# NanoEthernet.net
KiCad netlist of a schematic drawn in EAGLE
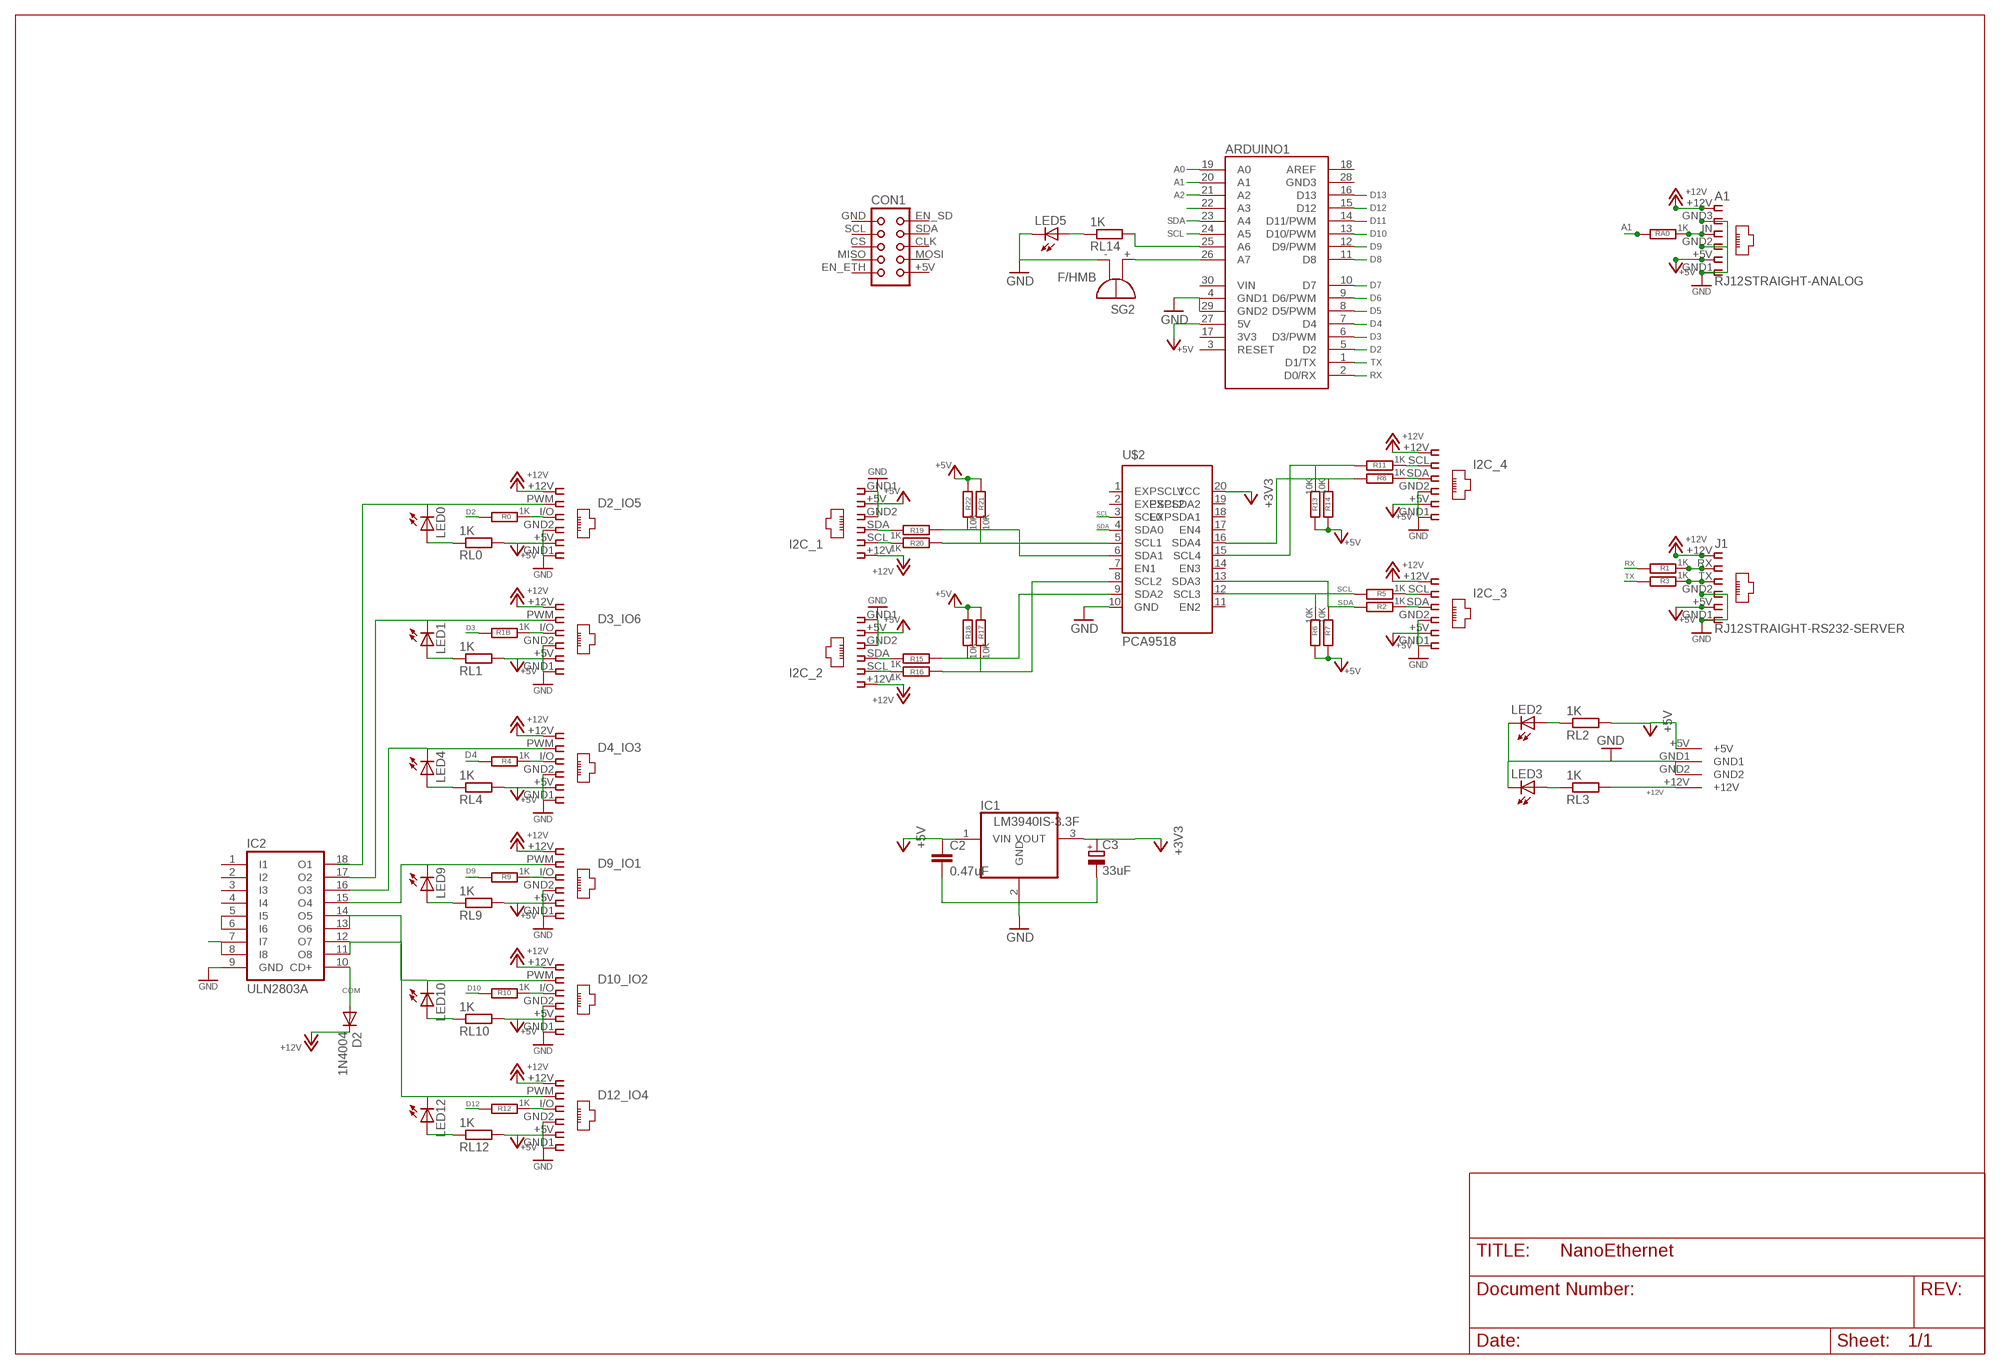
[diagram p0: schematic, sheet 1]

(export (version "E")
  (design (tool "Eeschema 10.0.6"))
  (components
    (comp (ref "A1")
      (value "RJ12STRAIGHT-ANALOG")
      (footprint "eagle-import:RJ12-STRAIGHT-ANALOG")
      (libsource (lib "eagle-import") (part "RJ12STRAIGHT-ANALOG"))
    )
    (comp (ref "ARDUINO1")
      (value "ARDUINO_NANO")
      (footprint "eagle-import:ARDUINO_NANO")
      (libsource (lib "eagle-import") (part "ARDUINO_NANO"))
    )
    (comp (ref "C2")
      (value "0.47uF")
      (footprint "eagle-import:C1206")
      (libsource (lib "eagle-import") (part "C-EUC1206"))
    )
    (comp (ref "C3")
      (value "33uF")
      (footprint "eagle-import:E3,5-8")
      (libsource (lib "eagle-import") (part "CPOL-EUE3.5-8"))
    )
    (comp (ref "CON1")
      (value "CON10EXT")
      (footprint "eagle-import:CON10EXT")
      (libsource (lib "eagle-import") (part "CON10EXT"))
    )
    (comp (ref "D2")
      (value "1N4004")
      (footprint "eagle-import:DO41-10")
      (libsource (lib "eagle-import") (part "1N4004"))
    )
    (comp (ref "D2_IO5")
      (value "IO5")
      (footprint "eagle-import:RJ12-STRAIGHT")
      (libsource (lib "eagle-import") (part "RJ12STRAIGHT"))
    )
    (comp (ref "D3_IO6")
      (value "IO6")
      (footprint "eagle-import:RJ12-STRAIGHT")
      (libsource (lib "eagle-import") (part "RJ12STRAIGHT"))
    )
    (comp (ref "D4_IO3")
      (value "IO3")
      (footprint "eagle-import:RJ12-STRAIGHT")
      (libsource (lib "eagle-import") (part "RJ12STRAIGHT"))
    )
    (comp (ref "D9_IO1")
      (value "IO1")
      (footprint "eagle-import:RJ12-STRAIGHT")
      (libsource (lib "eagle-import") (part "RJ12STRAIGHT"))
    )
    (comp (ref "D10_IO2")
      (value "IO2")
      (footprint "eagle-import:RJ12-STRAIGHT")
      (libsource (lib "eagle-import") (part "RJ12STRAIGHT"))
    )
    (comp (ref "D12_IO4")
      (value "IO4")
      (footprint "eagle-import:RJ12-STRAIGHT")
      (libsource (lib "eagle-import") (part "RJ12STRAIGHT"))
    )
    (comp (ref "I2C_1")
      (value "I2C")
      (footprint "eagle-import:RJ12-STRAIGHT-I2C")
      (libsource (lib "eagle-import") (part "RJ12STRAIGHT-I2C"))
    )
    (comp (ref "I2C_2")
      (value "I2C")
      (footprint "eagle-import:RJ12-STRAIGHT-I2C")
      (libsource (lib "eagle-import") (part "RJ12STRAIGHT-I2C"))
    )
    (comp (ref "I2C_3")
      (value "I2C")
      (footprint "eagle-import:RJ12-STRAIGHT-I2C")
      (libsource (lib "eagle-import") (part "RJ12STRAIGHT-I2C"))
    )
    (comp (ref "I2C_4")
      (value "I2C")
      (footprint "eagle-import:RJ12-STRAIGHT-I2C")
      (libsource (lib "eagle-import") (part "RJ12STRAIGHT-I2C"))
    )
    (comp (ref "IC1")
      (value "LM3940IS-3.3F")
      (footprint "eagle-import:DD-3")
      (fields (field (name "MF") "TEXAS INSTRUMENTS") (field (name "MPN") "REG1117FAKTTT"))
      (libsource (lib "eagle-import") (part "LM3940IS-3.3F"))
    )
    (comp (ref "IC2")
      (value "ULN2803A")
      (footprint "eagle-import:SO18W")
      (libsource (lib "eagle-import") (part "ULN2803A"))
    )
    (comp (ref "J1")
      (value "RJ12STRAIGHT-RS232-SERVER")
      (footprint "eagle-import:RJ12-STRAIGHT-RS232")
      (libsource (lib "eagle-import") (part "RJ12STRAIGHT-RS232-SERVER"))
    )
    (comp (ref "LED0")
      (value "LED3MM")
      (footprint "eagle-import:LED3MM")
      (libsource (lib "eagle-import") (part "LED3MM"))
    )
    (comp (ref "LED1")
      (value "LED3MM")
      (footprint "eagle-import:LED3MM")
      (libsource (lib "eagle-import") (part "LED3MM"))
    )
    (comp (ref "LED2")
      (value "LED3MM")
      (footprint "eagle-import:LED3MM")
      (libsource (lib "eagle-import") (part "LED3MM"))
    )
    (comp (ref "LED3")
      (value "LED3MM")
      (footprint "eagle-import:LED3MM")
      (libsource (lib "eagle-import") (part "LED3MM"))
    )
    (comp (ref "LED4")
      (value "LED3MM")
      (footprint "eagle-import:LED3MM")
      (libsource (lib "eagle-import") (part "LED3MM"))
    )
    (comp (ref "LED5")
      (value "LED3MM")
      (footprint "eagle-import:LED3MM")
      (libsource (lib "eagle-import") (part "LED3MM"))
    )
    (comp (ref "LED9")
      (value "LED3MM")
      (footprint "eagle-import:LED3MM")
      (libsource (lib "eagle-import") (part "LED3MM"))
    )
    (comp (ref "LED10")
      (value "LED3MM")
      (footprint "eagle-import:LED3MM")
      (libsource (lib "eagle-import") (part "LED3MM"))
    )
    (comp (ref "LED12")
      (value "LED3MM")
      (footprint "eagle-import:LED3MM")
      (libsource (lib "eagle-import") (part "LED3MM"))
    )
    (comp (ref "R0")
      (value "1K")
      (footprint "eagle-import:M1206")
      (libsource (lib "eagle-import") (part "R-EU_M1206"))
    )
    (comp (ref "R1")
      (value "1K")
      (footprint "eagle-import:M1206")
      (libsource (lib "eagle-import") (part "R-EU_M1206"))
    )
    (comp (ref "R1B")
      (value "1K")
      (footprint "eagle-import:M1206")
      (libsource (lib "eagle-import") (part "R-EU_M1206"))
    )
    (comp (ref "R2")
      (value "1K")
      (footprint "eagle-import:M1206")
      (libsource (lib "eagle-import") (part "R-EU_M1206"))
    )
    (comp (ref "R3")
      (value "1K")
      (footprint "eagle-import:M1206")
      (libsource (lib "eagle-import") (part "R-EU_M1206"))
    )
    (comp (ref "R4")
      (value "1K")
      (footprint "eagle-import:M1206")
      (libsource (lib "eagle-import") (part "R-EU_M1206"))
    )
    (comp (ref "R5")
      (value "1K")
      (footprint "eagle-import:M1206")
      (libsource (lib "eagle-import") (part "R-EU_M1206"))
    )
    (comp (ref "R6")
      (value "10K")
      (footprint "eagle-import:M1206")
      (libsource (lib "eagle-import") (part "R-EU_M1206"))
    )
    (comp (ref "R7")
      (value "10K")
      (footprint "eagle-import:M1206")
      (libsource (lib "eagle-import") (part "R-EU_M1206"))
    )
    (comp (ref "R8")
      (value "1K")
      (footprint "eagle-import:M1206")
      (libsource (lib "eagle-import") (part "R-EU_M1206"))
    )
    (comp (ref "R9")
      (value "1K")
      (footprint "eagle-import:M1206")
      (libsource (lib "eagle-import") (part "R-EU_M1206"))
    )
    (comp (ref "R10")
      (value "1K")
      (footprint "eagle-import:M1206")
      (libsource (lib "eagle-import") (part "R-EU_M1206"))
    )
    (comp (ref "R11")
      (value "1K")
      (footprint "eagle-import:M1206")
      (libsource (lib "eagle-import") (part "R-EU_M1206"))
    )
    (comp (ref "R12")
      (value "1K")
      (footprint "eagle-import:M1206")
      (libsource (lib "eagle-import") (part "R-EU_M1206"))
    )
    (comp (ref "R13")
      (value "10K")
      (footprint "eagle-import:M1206")
      (libsource (lib "eagle-import") (part "R-EU_M1206"))
    )
    (comp (ref "R14")
      (value "10K")
      (footprint "eagle-import:M1206")
      (libsource (lib "eagle-import") (part "R-EU_M1206"))
    )
    (comp (ref "R15")
      (value "1K")
      (footprint "eagle-import:M1206")
      (libsource (lib "eagle-import") (part "R-EU_M1206"))
    )
    (comp (ref "R16")
      (value "1K")
      (footprint "eagle-import:M1206")
      (libsource (lib "eagle-import") (part "R-EU_M1206"))
    )
    (comp (ref "R17")
      (value "10K")
      (footprint "eagle-import:M1206")
      (libsource (lib "eagle-import") (part "R-EU_M1206"))
    )
    (comp (ref "R18")
      (value "10K")
      (footprint "eagle-import:M1206")
      (libsource (lib "eagle-import") (part "R-EU_M1206"))
    )
    (comp (ref "R19")
      (value "1K")
      (footprint "eagle-import:M1206")
      (libsource (lib "eagle-import") (part "R-EU_M1206"))
    )
    (comp (ref "R20")
      (value "1K")
      (footprint "eagle-import:M1206")
      (libsource (lib "eagle-import") (part "R-EU_M1206"))
    )
    (comp (ref "R21")
      (value "10K")
      (footprint "eagle-import:M1206")
      (libsource (lib "eagle-import") (part "R-EU_M1206"))
    )
    (comp (ref "R22")
      (value "10K")
      (footprint "eagle-import:M1206")
      (libsource (lib "eagle-import") (part "R-EU_M1206"))
    )
    (comp (ref "RA0")
      (value "1K")
      (footprint "eagle-import:M1206")
      (libsource (lib "eagle-import") (part "R-EU_M1206"))
    )
    (comp (ref "RL0")
      (value "1K")
      (footprint "eagle-import:M1206")
      (libsource (lib "eagle-import") (part "R-EU_M1206"))
    )
    (comp (ref "RL1")
      (value "1K")
      (footprint "eagle-import:M1206")
      (libsource (lib "eagle-import") (part "R-EU_M1206"))
    )
    (comp (ref "RL2")
      (value "1K")
      (footprint "eagle-import:M1206")
      (libsource (lib "eagle-import") (part "R-EU_M1206"))
    )
    (comp (ref "RL3")
      (value "1K")
      (footprint "eagle-import:M1206")
      (libsource (lib "eagle-import") (part "R-EU_M1206"))
    )
    (comp (ref "RL4")
      (value "1K")
      (footprint "eagle-import:M1206")
      (libsource (lib "eagle-import") (part "R-EU_M1206"))
    )
    (comp (ref "RL9")
      (value "1K")
      (footprint "eagle-import:M1206")
      (libsource (lib "eagle-import") (part "R-EU_M1206"))
    )
    (comp (ref "RL10")
      (value "1K")
      (footprint "eagle-import:M1206")
      (libsource (lib "eagle-import") (part "R-EU_M1206"))
    )
    (comp (ref "RL12")
      (value "1K")
      (footprint "eagle-import:M1206")
      (libsource (lib "eagle-import") (part "R-EU_M1206"))
    )
    (comp (ref "RL14")
      (value "1K")
      (footprint "eagle-import:M1206")
      (libsource (lib "eagle-import") (part "R-EU_M1206"))
    )
    (comp (ref "SG2")
      (value "F/HMB")
      (footprint "eagle-import:F_HMB")
      (libsource (lib "eagle-import") (part "F/HMB"))
    )
    (comp (ref "U$1")
      (value "KPJX-4S-S")
      (footprint "eagle-import:KPJX-4S-S")
      (libsource (lib "eagle-import") (part "KPJX-4S-S"))
    )
    (comp (ref "U$2")
      (value "PCA9518")
      (footprint "eagle-import:SO20W")
      (libsource (lib "eagle-import") (part "PCA9518"))
    )
  )
  (nets
    (net (code "1") (name "+3V3") (class "Default")
      (node (ref "C3") (pin "+") (pinfunction "+_+") (pintype "passive"))
      (node (ref "IC1") (pin "3") (pinfunction "VOUT_3") (pintype "output"))
      (node (ref "U$2") (pin "20") (pinfunction "VCC_20") (pintype "power_in"))
    )
    (net (code "2") (name "+5V") (class "Default")
      (node (ref "A1") (pin "+5V") (pinfunction "5_+5V") (pintype "power_in"))
      (node (ref "ARDUINO1") (pin "27") (pinfunction "5V_27") (pintype "power_in"))
      (node (ref "C2") (pin "1") (pinfunction "1_1") (pintype "passive"))
      (node (ref "D10_IO2") (pin "+5V") (pinfunction "5_+5V") (pintype "power_in"))
      (node (ref "D12_IO4") (pin "+5V") (pinfunction "5_+5V") (pintype "power_in"))
      (node (ref "D2_IO5") (pin "+5V") (pinfunction "5_+5V") (pintype "power_in"))
      (node (ref "D3_IO6") (pin "+5V") (pinfunction "5_+5V") (pintype "power_in"))
      (node (ref "D4_IO3") (pin "+5V") (pinfunction "5_+5V") (pintype "power_in"))
      (node (ref "D9_IO1") (pin "+5V") (pinfunction "5_+5V") (pintype "power_in"))
      (node (ref "I2C_1") (pin "+5V") (pinfunction "5_+5V") (pintype "power_in"))
      (node (ref "I2C_2") (pin "+5V") (pinfunction "5_+5V") (pintype "power_in"))
      (node (ref "I2C_3") (pin "+5V") (pinfunction "5_+5V") (pintype "power_in"))
      (node (ref "I2C_4") (pin "+5V") (pinfunction "5_+5V") (pintype "power_in"))
      (node (ref "IC1") (pin "1") (pinfunction "VIN_1") (pintype "input"))
      (node (ref "J1") (pin "+5V") (pinfunction "5_+5V") (pintype "power_in"))
      (node (ref "R13") (pin "2") (pinfunction "2_2") (pintype "passive"))
      (node (ref "R14") (pin "2") (pinfunction "2_2") (pintype "passive"))
      (node (ref "R17") (pin "2") (pinfunction "2_2") (pintype "passive"))
      (node (ref "R18") (pin "2") (pinfunction "2_2") (pintype "passive"))
      (node (ref "R21") (pin "2") (pinfunction "2_2") (pintype "passive"))
      (node (ref "R22") (pin "2") (pinfunction "2_2") (pintype "passive"))
      (node (ref "R6") (pin "2") (pinfunction "2_2") (pintype "passive"))
      (node (ref "R7") (pin "2") (pinfunction "2_2") (pintype "passive"))
      (node (ref "RL0") (pin "2") (pinfunction "2_2") (pintype "passive"))
      (node (ref "RL1") (pin "2") (pinfunction "2_2") (pintype "passive"))
      (node (ref "RL10") (pin "2") (pinfunction "2_2") (pintype "passive"))
      (node (ref "RL12") (pin "2") (pinfunction "2_2") (pintype "passive"))
      (node (ref "RL2") (pin "2") (pinfunction "2_2") (pintype "passive"))
      (node (ref "RL4") (pin "2") (pinfunction "2_2") (pintype "passive"))
      (node (ref "RL9") (pin "2") (pinfunction "2_2") (pintype "passive"))
      (node (ref "U$1") (pin "+5V") (pinfunction "+5V_+5V") (pintype "power_in"))
    )
    (net (code "3") (name "+12V") (class "Default")
      (node (ref "A1") (pin "+12V") (pinfunction "1_+12V") (pintype "power_in"))
      (node (ref "D10_IO2") (pin "+12V") (pinfunction "1_+12V") (pintype "power_in"))
      (node (ref "D12_IO4") (pin "+12V") (pinfunction "1_+12V") (pintype "power_in"))
      (node (ref "D2") (pin "C") (pinfunction "C_C") (pintype "passive"))
      (node (ref "D2_IO5") (pin "+12V") (pinfunction "1_+12V") (pintype "power_in"))
      (node (ref "D3_IO6") (pin "+12V") (pinfunction "1_+12V") (pintype "power_in"))
      (node (ref "D4_IO3") (pin "+12V") (pinfunction "1_+12V") (pintype "power_in"))
      (node (ref "D9_IO1") (pin "+12V") (pinfunction "1_+12V") (pintype "power_in"))
      (node (ref "I2C_1") (pin "+12V") (pinfunction "1_+12V") (pintype "power_in"))
      (node (ref "I2C_2") (pin "+12V") (pinfunction "1_+12V") (pintype "power_in"))
      (node (ref "I2C_3") (pin "+12V") (pinfunction "1_+12V") (pintype "power_in"))
      (node (ref "I2C_4") (pin "+12V") (pinfunction "1_+12V") (pintype "power_in"))
      (node (ref "J1") (pin "+12V") (pinfunction "1_+12V") (pintype "power_in"))
      (node (ref "RL3") (pin "2") (pinfunction "2_2") (pintype "passive"))
      (node (ref "U$1") (pin "+12V") (pinfunction "+12V_+12V") (pintype "power_in"))
    )
    (net (code "4") (name "/3V3") (class "Default")
      (node (ref "ARDUINO1") (pin "17") (pinfunction "3V3_17") (pintype "power_in"))
    )
    (net (code "5") (name "/A0") (class "Default")
      (node (ref "ARDUINO1") (pin "19") (pinfunction "A0_19") (pintype "bidirectional"))
    )
    (net (code "6") (name "/A1") (class "Default")
      (node (ref "ARDUINO1") (pin "20") (pinfunction "A1_20") (pintype "bidirectional"))
      (node (ref "RA0") (pin "2") (pinfunction "2_2") (pintype "passive"))
    )
    (net (code "7") (name "/A2") (class "Default")
      (node (ref "ARDUINO1") (pin "21") (pinfunction "A2_21") (pintype "bidirectional"))
    )
    (net (code "8") (name "/COM") (class "Default")
      (node (ref "D2") (pin "A") (pinfunction "A_A") (pintype "passive"))
      (node (ref "IC2") (pin "10") (pinfunction "CD+_10") (pintype "passive"))
    )
    (net (code "9") (name "/D2") (class "Default")
      (node (ref "ARDUINO1") (pin "5") (pinfunction "D2_5") (pintype "bidirectional"))
      (node (ref "R0") (pin "2") (pinfunction "2_2") (pintype "passive"))
    )
    (net (code "10") (name "/D3") (class "Default")
      (node (ref "ARDUINO1") (pin "6") (pinfunction "D3/PWM_6") (pintype "bidirectional"))
      (node (ref "R1B") (pin "2") (pinfunction "2_2") (pintype "passive"))
    )
    (net (code "11") (name "/D4") (class "Default")
      (node (ref "ARDUINO1") (pin "7") (pinfunction "D4_7") (pintype "bidirectional"))
      (node (ref "R4") (pin "2") (pinfunction "2_2") (pintype "passive"))
    )
    (net (code "12") (name "/D5") (class "Default")
      (node (ref "ARDUINO1") (pin "8") (pinfunction "D5/PWM_8") (pintype "bidirectional"))
    )
    (net (code "13") (name "/D6") (class "Default")
      (node (ref "ARDUINO1") (pin "9") (pinfunction "D6/PWM_9") (pintype "bidirectional"))
    )
    (net (code "14") (name "/D7") (class "Default")
      (node (ref "ARDUINO1") (pin "10") (pinfunction "D7_10") (pintype "bidirectional"))
    )
    (net (code "15") (name "/D8") (class "Default")
      (node (ref "ARDUINO1") (pin "11") (pinfunction "D8_11") (pintype "bidirectional"))
    )
    (net (code "16") (name "/D9") (class "Default")
      (node (ref "ARDUINO1") (pin "12") (pinfunction "D9/PWM_12") (pintype "bidirectional"))
      (node (ref "R9") (pin "2") (pinfunction "2_2") (pintype "passive"))
    )
    (net (code "17") (name "/D10") (class "Default")
      (node (ref "ARDUINO1") (pin "13") (pinfunction "D10/PWM_13") (pintype "bidirectional"))
      (node (ref "IC2") (pin "5") (pinfunction "I5_5") (pintype "input"))
      (node (ref "IC2") (pin "6") (pinfunction "I6_6") (pintype "input"))
      (node (ref "R10") (pin "2") (pinfunction "2_2") (pintype "passive"))
    )
    (net (code "18") (name "/D11") (class "Default")
      (node (ref "ARDUINO1") (pin "14") (pinfunction "D11/PWM_14") (pintype "bidirectional"))
    )
    (net (code "19") (name "/D12") (class "Default")
      (node (ref "ARDUINO1") (pin "15") (pinfunction "D12_15") (pintype "bidirectional"))
      (node (ref "IC2") (pin "7") (pinfunction "I7_7") (pintype "input"))
      (node (ref "IC2") (pin "8") (pinfunction "I8_8") (pintype "input"))
      (node (ref "R12") (pin "2") (pinfunction "2_2") (pintype "passive"))
    )
    (net (code "20") (name "/D13") (class "Default")
      (node (ref "ARDUINO1") (pin "16") (pinfunction "D13_16") (pintype "bidirectional"))
    )
    (net (code "21") (name "/RX") (class "Default")
      (node (ref "ARDUINO1") (pin "2") (pinfunction "D0/RX_2") (pintype "bidirectional"))
      (node (ref "R1") (pin "2") (pinfunction "2_2") (pintype "passive"))
    )
    (net (code "22") (name "/SCL") (class "Default")
      (node (ref "ARDUINO1") (pin "24") (pinfunction "A5_24") (pintype "bidirectional"))
      (node (ref "R5") (pin "2") (pinfunction "2_2") (pintype "passive"))
      (node (ref "R6") (pin "1") (pinfunction "1_1") (pintype "passive"))
      (node (ref "U$2") (pin "12") (pinfunction "SCL3_12") (pintype "bidirectional"))
      (node (ref "U$2") (pin "3") (pinfunction "SCL0_3") (pintype "bidirectional"))
    )
    (net (code "23") (name "/SDA") (class "Default")
      (node (ref "ARDUINO1") (pin "23") (pinfunction "A4_23") (pintype "bidirectional"))
      (node (ref "R2") (pin "2") (pinfunction "2_2") (pintype "passive"))
      (node (ref "R7") (pin "1") (pinfunction "1_1") (pintype "passive"))
      (node (ref "U$2") (pin "13") (pinfunction "SDA3_13") (pintype "bidirectional"))
      (node (ref "U$2") (pin "4") (pinfunction "SDA0_4") (pintype "bidirectional"))
    )
    (net (code "24") (name "/TX") (class "Default")
      (node (ref "ARDUINO1") (pin "1") (pinfunction "D1/TX_1") (pintype "bidirectional"))
      (node (ref "R3") (pin "2") (pinfunction "2_2") (pintype "passive"))
    )
    (net (code "25") (name "GND") (class "Default")
      (node (ref "A1") (pin "GND1") (pinfunction "6_GND1") (pintype "power_in"))
      (node (ref "A1") (pin "GND2") (pinfunction "4_GND2") (pintype "power_in"))
      (node (ref "A1") (pin "GND3") (pinfunction "2_GND3") (pintype "bidirectional"))
      (node (ref "ARDUINO1") (pin "29") (pinfunction "GND2_29") (pintype "power_in"))
      (node (ref "ARDUINO1") (pin "4") (pinfunction "GND1_4") (pintype "power_in"))
      (node (ref "C2") (pin "2") (pinfunction "2_2") (pintype "passive"))
      (node (ref "C3") (pin "-") (pinfunction "-_-") (pintype "passive"))
      (node (ref "D10_IO2") (pin "GND1") (pinfunction "6_GND1") (pintype "power_in"))
      (node (ref "D10_IO2") (pin "GND2") (pinfunction "4_GND2") (pintype "power_in"))
      (node (ref "D12_IO4") (pin "GND1") (pinfunction "6_GND1") (pintype "power_in"))
      (node (ref "D12_IO4") (pin "GND2") (pinfunction "4_GND2") (pintype "power_in"))
      (node (ref "D2_IO5") (pin "GND1") (pinfunction "6_GND1") (pintype "power_in"))
      (node (ref "D2_IO5") (pin "GND2") (pinfunction "4_GND2") (pintype "power_in"))
      (node (ref "D3_IO6") (pin "GND1") (pinfunction "6_GND1") (pintype "power_in"))
      (node (ref "D3_IO6") (pin "GND2") (pinfunction "4_GND2") (pintype "power_in"))
      (node (ref "D4_IO3") (pin "GND1") (pinfunction "6_GND1") (pintype "power_in"))
      (node (ref "D4_IO3") (pin "GND2") (pinfunction "4_GND2") (pintype "power_in"))
      (node (ref "D9_IO1") (pin "GND1") (pinfunction "6_GND1") (pintype "power_in"))
      (node (ref "D9_IO1") (pin "GND2") (pinfunction "4_GND2") (pintype "power_in"))
      (node (ref "I2C_1") (pin "GND1") (pinfunction "6_GND1") (pintype "power_in"))
      (node (ref "I2C_1") (pin "GND2") (pinfunction "4_GND2") (pintype "power_in"))
      (node (ref "I2C_2") (pin "GND1") (pinfunction "6_GND1") (pintype "power_in"))
      (node (ref "I2C_2") (pin "GND2") (pinfunction "4_GND2") (pintype "power_in"))
      (node (ref "I2C_3") (pin "GND1") (pinfunction "6_GND1") (pintype "power_in"))
      (node (ref "I2C_3") (pin "GND2") (pinfunction "4_GND2") (pintype "power_in"))
      (node (ref "I2C_4") (pin "GND1") (pinfunction "6_GND1") (pintype "power_in"))
      (node (ref "I2C_4") (pin "GND2") (pinfunction "4_GND2") (pintype "power_in"))
      (node (ref "IC1") (pin "2") (pinfunction "GND_2") (pintype "power_in"))
      (node (ref "IC2") (pin "9") (pinfunction "GND_9") (pintype "power_in"))
      (node (ref "J1") (pin "GND1") (pinfunction "6_GND1") (pintype "power_in"))
      (node (ref "J1") (pin "GND2") (pinfunction "4_GND2") (pintype "power_in"))
      (node (ref "LED2") (pin "K") (pinfunction "C_K") (pintype "passive"))
      (node (ref "LED3") (pin "K") (pinfunction "C_K") (pintype "passive"))
      (node (ref "LED5") (pin "K") (pinfunction "C_K") (pintype "passive"))
      (node (ref "SG2") (pin "-") (pinfunction "-_-") (pintype "passive"))
      (node (ref "U$1") (pin "GND1") (pinfunction "GND1_GND1") (pintype "input"))
      (node (ref "U$1") (pin "GND2") (pinfunction "GND2_GND2") (pintype "input"))
      (node (ref "U$2") (pin "10") (pinfunction "GND_10") (pintype "power_in"))
    )
    (net (code "26") (name "Net-(A1-3)") (class "Default")
      (node (ref "A1") (pin "IN") (pinfunction "3_IN") (pintype "bidirectional"))
      (node (ref "RA0") (pin "1") (pinfunction "1_1") (pintype "passive"))
    )
    (net (code "27") (name "Net-(ARDUINO1-A6)") (class "Default")
      (node (ref "ARDUINO1") (pin "25") (pinfunction "A6_25") (pintype "bidirectional"))
      (node (ref "RL14") (pin "2") (pinfunction "2_2") (pintype "passive"))
    )
    (net (code "28") (name "Net-(ARDUINO1-A7)") (class "Default")
      (node (ref "ARDUINO1") (pin "26") (pinfunction "A7_26") (pintype "bidirectional"))
      (node (ref "SG2") (pin "+") (pinfunction "+_+") (pintype "passive"))
    )
    (net (code "29") (name "Net-(D2_IO5-2)") (class "Default")
      (node (ref "D2_IO5") (pin "PWM") (pinfunction "2_PWM") (pintype "bidirectional"))
      (node (ref "LED0") (pin "K") (pinfunction "C_K") (pintype "passive"))
    )
    (net (code "30") (name "Net-(D2_IO5-3)") (class "Default")
      (node (ref "D2_IO5") (pin "I/O") (pinfunction "3_I/O") (pintype "bidirectional"))
      (node (ref "R0") (pin "1") (pinfunction "1_1") (pintype "passive"))
    )
    (net (code "31") (name "Net-(D3_IO6-2)") (class "Default")
      (node (ref "D3_IO6") (pin "PWM") (pinfunction "2_PWM") (pintype "bidirectional"))
      (node (ref "IC2") (pin "17") (pinfunction "O2_17") (pintype "open_collector"))
      (node (ref "LED1") (pin "K") (pinfunction "C_K") (pintype "passive"))
    )
    (net (code "32") (name "Net-(D3_IO6-3)") (class "Default")
      (node (ref "D3_IO6") (pin "I/O") (pinfunction "3_I/O") (pintype "bidirectional"))
      (node (ref "R1B") (pin "1") (pinfunction "1_1") (pintype "passive"))
    )
    (net (code "33") (name "Net-(D4_IO3-2)") (class "Default")
      (node (ref "D4_IO3") (pin "PWM") (pinfunction "2_PWM") (pintype "bidirectional"))
      (node (ref "IC2") (pin "16") (pinfunction "O3_16") (pintype "open_collector"))
      (node (ref "LED4") (pin "K") (pinfunction "C_K") (pintype "passive"))
    )
    (net (code "34") (name "Net-(D4_IO3-3)") (class "Default")
      (node (ref "D4_IO3") (pin "I/O") (pinfunction "3_I/O") (pintype "bidirectional"))
      (node (ref "R4") (pin "1") (pinfunction "1_1") (pintype "passive"))
    )
    (net (code "35") (name "Net-(D9_IO1-2)") (class "Default")
      (node (ref "D9_IO1") (pin "PWM") (pinfunction "2_PWM") (pintype "bidirectional"))
      (node (ref "IC2") (pin "15") (pinfunction "O4_15") (pintype "open_collector"))
      (node (ref "LED9") (pin "K") (pinfunction "C_K") (pintype "passive"))
    )
    (net (code "36") (name "Net-(D9_IO1-3)") (class "Default")
      (node (ref "D9_IO1") (pin "I/O") (pinfunction "3_I/O") (pintype "bidirectional"))
      (node (ref "R9") (pin "1") (pinfunction "1_1") (pintype "passive"))
    )
    (net (code "37") (name "Net-(D10_IO2-2)") (class "Default")
      (node (ref "D10_IO2") (pin "PWM") (pinfunction "2_PWM") (pintype "bidirectional"))
      (node (ref "IC2") (pin "13") (pinfunction "O6_13") (pintype "open_collector"))
      (node (ref "IC2") (pin "14") (pinfunction "O5_14") (pintype "open_collector"))
      (node (ref "LED10") (pin "K") (pinfunction "C_K") (pintype "passive"))
    )
    (net (code "38") (name "Net-(D10_IO2-3)") (class "Default")
      (node (ref "D10_IO2") (pin "I/O") (pinfunction "3_I/O") (pintype "bidirectional"))
      (node (ref "R10") (pin "1") (pinfunction "1_1") (pintype "passive"))
    )
    (net (code "39") (name "Net-(D12_IO4-2)") (class "Default")
      (node (ref "D12_IO4") (pin "PWM") (pinfunction "2_PWM") (pintype "bidirectional"))
      (node (ref "IC2") (pin "11") (pinfunction "O8_11") (pintype "open_collector"))
      (node (ref "IC2") (pin "12") (pinfunction "O7_12") (pintype "open_collector"))
      (node (ref "LED12") (pin "K") (pinfunction "C_K") (pintype "passive"))
    )
    (net (code "40") (name "Net-(D12_IO4-3)") (class "Default")
      (node (ref "D12_IO4") (pin "I/O") (pinfunction "3_I/O") (pintype "bidirectional"))
      (node (ref "R12") (pin "1") (pinfunction "1_1") (pintype "passive"))
    )
    (net (code "41") (name "Net-(I2C_1-2)") (class "Default")
      (node (ref "I2C_1") (pin "SCL") (pinfunction "2_SCL") (pintype "bidirectional"))
      (node (ref "R20") (pin "1") (pinfunction "1_1") (pintype "passive"))
    )
    (net (code "42") (name "Net-(I2C_1-3)") (class "Default")
      (node (ref "I2C_1") (pin "SDA") (pinfunction "3_SDA") (pintype "bidirectional"))
      (node (ref "R19") (pin "1") (pinfunction "1_1") (pintype "passive"))
    )
    (net (code "43") (name "Net-(I2C_2-2)") (class "Default")
      (node (ref "I2C_2") (pin "SCL") (pinfunction "2_SCL") (pintype "bidirectional"))
      (node (ref "R16") (pin "1") (pinfunction "1_1") (pintype "passive"))
    )
    (net (code "44") (name "Net-(I2C_2-3)") (class "Default")
      (node (ref "I2C_2") (pin "SDA") (pinfunction "3_SDA") (pintype "bidirectional"))
      (node (ref "R15") (pin "1") (pinfunction "1_1") (pintype "passive"))
    )
    (net (code "45") (name "Net-(I2C_3-2)") (class "Default")
      (node (ref "I2C_3") (pin "SCL") (pinfunction "2_SCL") (pintype "bidirectional"))
      (node (ref "R5") (pin "1") (pinfunction "1_1") (pintype "passive"))
    )
    (net (code "46") (name "Net-(I2C_3-3)") (class "Default")
      (node (ref "I2C_3") (pin "SDA") (pinfunction "3_SDA") (pintype "bidirectional"))
      (node (ref "R2") (pin "1") (pinfunction "1_1") (pintype "passive"))
    )
    (net (code "47") (name "Net-(I2C_4-2)") (class "Default")
      (node (ref "I2C_4") (pin "SCL") (pinfunction "2_SCL") (pintype "bidirectional"))
      (node (ref "R11") (pin "1") (pinfunction "1_1") (pintype "passive"))
    )
    (net (code "48") (name "Net-(I2C_4-3)") (class "Default")
      (node (ref "I2C_4") (pin "SDA") (pinfunction "3_SDA") (pintype "bidirectional"))
      (node (ref "R8") (pin "1") (pinfunction "1_1") (pintype "passive"))
    )
    (net (code "49") (name "Net-(J1-2)") (class "Default")
      (node (ref "J1") (pin "RX") (pinfunction "2_RX") (pintype "bidirectional"))
      (node (ref "R1") (pin "1") (pinfunction "1_1") (pintype "passive"))
    )
    (net (code "50") (name "Net-(J1-3)") (class "Default")
      (node (ref "J1") (pin "TX") (pinfunction "3_TX") (pintype "bidirectional"))
      (node (ref "R3") (pin "1") (pinfunction "1_1") (pintype "passive"))
    )
    (net (code "51") (name "Net-(LED0-PadA)") (class "Default")
      (node (ref "LED0") (pin "A") (pinfunction "A_A") (pintype "passive"))
      (node (ref "RL0") (pin "1") (pinfunction "1_1") (pintype "passive"))
    )
    (net (code "52") (name "Net-(LED1-PadA)") (class "Default")
      (node (ref "LED1") (pin "A") (pinfunction "A_A") (pintype "passive"))
      (node (ref "RL1") (pin "1") (pinfunction "1_1") (pintype "passive"))
    )
    (net (code "53") (name "Net-(LED2-PadA)") (class "Default")
      (node (ref "LED2") (pin "A") (pinfunction "A_A") (pintype "passive"))
      (node (ref "RL2") (pin "1") (pinfunction "1_1") (pintype "passive"))
    )
    (net (code "54") (name "Net-(LED3-PadA)") (class "Default")
      (node (ref "LED3") (pin "A") (pinfunction "A_A") (pintype "passive"))
      (node (ref "RL3") (pin "1") (pinfunction "1_1") (pintype "passive"))
    )
    (net (code "55") (name "Net-(LED4-PadA)") (class "Default")
      (node (ref "LED4") (pin "A") (pinfunction "A_A") (pintype "passive"))
      (node (ref "RL4") (pin "1") (pinfunction "1_1") (pintype "passive"))
    )
    (net (code "56") (name "Net-(LED5-PadA)") (class "Default")
      (node (ref "LED5") (pin "A") (pinfunction "A_A") (pintype "passive"))
      (node (ref "RL14") (pin "1") (pinfunction "1_1") (pintype "passive"))
    )
    (net (code "57") (name "Net-(LED9-PadA)") (class "Default")
      (node (ref "LED9") (pin "A") (pinfunction "A_A") (pintype "passive"))
      (node (ref "RL9") (pin "1") (pinfunction "1_1") (pintype "passive"))
    )
    (net (code "58") (name "Net-(LED10-PadA)") (class "Default")
      (node (ref "LED10") (pin "A") (pinfunction "A_A") (pintype "passive"))
      (node (ref "RL10") (pin "1") (pinfunction "1_1") (pintype "passive"))
    )
    (net (code "59") (name "Net-(LED12-PadA)") (class "Default")
      (node (ref "LED12") (pin "A") (pinfunction "A_A") (pintype "passive"))
      (node (ref "RL12") (pin "1") (pinfunction "1_1") (pintype "passive"))
    )
    (net (code "60") (name "Net-(U$2-SCL1)") (class "Default")
      (node (ref "R20") (pin "2") (pinfunction "2_2") (pintype "passive"))
      (node (ref "R21") (pin "1") (pinfunction "1_1") (pintype "passive"))
      (node (ref "U$2") (pin "5") (pinfunction "SCL1_5") (pintype "bidirectional"))
    )
    (net (code "61") (name "Net-(U$2-SCL2)") (class "Default")
      (node (ref "R16") (pin "2") (pinfunction "2_2") (pintype "passive"))
      (node (ref "R17") (pin "1") (pinfunction "1_1") (pintype "passive"))
      (node (ref "U$2") (pin "8") (pinfunction "SCL2_8") (pintype "bidirectional"))
    )
    (net (code "62") (name "Net-(U$2-SCL4)") (class "Default")
      (node (ref "R11") (pin "2") (pinfunction "2_2") (pintype "passive"))
      (node (ref "R13") (pin "1") (pinfunction "1_1") (pintype "passive"))
      (node (ref "U$2") (pin "15") (pinfunction "SCL4_15") (pintype "bidirectional"))
    )
    (net (code "63") (name "Net-(U$2-SDA1)") (class "Default")
      (node (ref "R19") (pin "2") (pinfunction "2_2") (pintype "passive"))
      (node (ref "R22") (pin "1") (pinfunction "1_1") (pintype "passive"))
      (node (ref "U$2") (pin "6") (pinfunction "SDA1_6") (pintype "bidirectional"))
    )
    (net (code "64") (name "Net-(U$2-SDA2)") (class "Default")
      (node (ref "R15") (pin "2") (pinfunction "2_2") (pintype "passive"))
      (node (ref "R18") (pin "1") (pinfunction "1_1") (pintype "passive"))
      (node (ref "U$2") (pin "9") (pinfunction "SDA2_9") (pintype "bidirectional"))
    )
    (net (code "65") (name "Net-(U$2-SDA4)") (class "Default")
      (node (ref "R14") (pin "1") (pinfunction "1_1") (pintype "passive"))
      (node (ref "R8") (pin "2") (pinfunction "2_2") (pintype "passive"))
      (node (ref "U$2") (pin "16") (pinfunction "SDA4_16") (pintype "bidirectional"))
    )
    (net (code "66") (name "unconnected-(ARDUINO1-A3-Pad22)") (class "Default")
      (node (ref "ARDUINO1") (pin "22") (pinfunction "A3_22") (pintype "bidirectional"))
    )
    (net (code "67") (name "unconnected-(ARDUINO1-AREF-Pad18)") (class "Default")
      (node (ref "ARDUINO1") (pin "18") (pinfunction "AREF_18") (pintype "bidirectional"))
    )
    (net (code "68") (name "unconnected-(ARDUINO1-GND3-Pad28)") (class "Default")
      (node (ref "ARDUINO1") (pin "28") (pinfunction "GND3_28") (pintype "bidirectional"))
    )
    (net (code "69") (name "unconnected-(ARDUINO1-RESET-Pad3)") (class "Default")
      (node (ref "ARDUINO1") (pin "3") (pinfunction "RESET_3") (pintype "bidirectional"))
    )
    (net (code "70") (name "unconnected-(ARDUINO1-VIN-Pad30)") (class "Default")
      (node (ref "ARDUINO1") (pin "30") (pinfunction "VIN_30") (pintype "bidirectional"))
    )
    (net (code "71") (name "unconnected-(CON1-1-Pad+5V)") (class "Default")
      (node (ref "CON1") (pin "+5V") (pinfunction "1_+5V") (pintype "passive"))
    )
    (net (code "72") (name "unconnected-(CON1-2-PadEN_ETH)") (class "Default")
      (node (ref "CON1") (pin "EN_ETH") (pinfunction "2_EN_ETH") (pintype "passive"))
    )
    (net (code "73") (name "unconnected-(CON1-3-PadMOSI)") (class "Default")
      (node (ref "CON1") (pin "MOSI") (pinfunction "3_MOSI") (pintype "passive"))
    )
    (net (code "74") (name "unconnected-(CON1-4-PadMISO)") (class "Default")
      (node (ref "CON1") (pin "MISO") (pinfunction "4_MISO") (pintype "passive"))
    )
    (net (code "75") (name "unconnected-(CON1-5-PadCLK)") (class "Default")
      (node (ref "CON1") (pin "CLK") (pinfunction "5_CLK") (pintype "passive"))
    )
    (net (code "76") (name "unconnected-(CON1-6-PadCS)") (class "Default")
      (node (ref "CON1") (pin "CS") (pinfunction "6_CS") (pintype "passive"))
    )
    (net (code "77") (name "unconnected-(CON1-7-PadSDA)") (class "Default")
      (node (ref "CON1") (pin "SDA") (pinfunction "7_SDA") (pintype "passive"))
    )
    (net (code "78") (name "unconnected-(CON1-8-PadSCL)") (class "Default")
      (node (ref "CON1") (pin "SCL") (pinfunction "8_SCL") (pintype "passive"))
    )
    (net (code "79") (name "unconnected-(CON1-9-PadEN_SD)") (class "Default")
      (node (ref "CON1") (pin "EN_SD") (pinfunction "9_EN_SD") (pintype "passive"))
    )
    (net (code "80") (name "unconnected-(CON1-10-PadGND)") (class "Default")
      (node (ref "CON1") (pin "GND") (pinfunction "10_GND") (pintype "passive"))
    )
    (net (code "81") (name "unconnected-(IC2-I1-Pad1)") (class "Default")
      (node (ref "IC2") (pin "1") (pinfunction "I1_1") (pintype "input"))
    )
    (net (code "82") (name "unconnected-(IC2-I2-Pad2)") (class "Default")
      (node (ref "IC2") (pin "2") (pinfunction "I2_2") (pintype "input"))
    )
    (net (code "83") (name "unconnected-(IC2-I3-Pad3)") (class "Default")
      (node (ref "IC2") (pin "3") (pinfunction "I3_3") (pintype "input"))
    )
    (net (code "84") (name "unconnected-(IC2-I4-Pad4)") (class "Default")
      (node (ref "IC2") (pin "4") (pinfunction "I4_4") (pintype "input"))
    )
    (net (code "85") (name "unconnected-(IC2-O1-Pad18)") (class "Default")
      (node (ref "IC2") (pin "18") (pinfunction "O1_18") (pintype "open_collector"))
    )
    (net (code "86") (name "unconnected-(U$2-EN1-Pad7)") (class "Default")
      (node (ref "U$2") (pin "7") (pinfunction "EN1_7") (pintype "input"))
    )
    (net (code "87") (name "unconnected-(U$2-EN2-Pad11)") (class "Default")
      (node (ref "U$2") (pin "11") (pinfunction "EN2_11") (pintype "input"))
    )
    (net (code "88") (name "unconnected-(U$2-EN3-Pad14)") (class "Default")
      (node (ref "U$2") (pin "14") (pinfunction "EN3_14") (pintype "input"))
    )
    (net (code "89") (name "unconnected-(U$2-EN4-Pad17)") (class "Default")
      (node (ref "U$2") (pin "17") (pinfunction "EN4_17") (pintype "input"))
    )
    (net (code "90") (name "unconnected-(U$2-EXPSCL1-Pad1)") (class "Default")
      (node (ref "U$2") (pin "1") (pinfunction "EXPSCL1_1") (pintype "bidirectional"))
    )
    (net (code "91") (name "unconnected-(U$2-EXPSCL2-Pad2)") (class "Default")
      (node (ref "U$2") (pin "2") (pinfunction "EXPSCL2_2") (pintype "bidirectional"))
    )
    (net (code "92") (name "unconnected-(U$2-EXPSDA1-Pad18)") (class "Default")
      (node (ref "U$2") (pin "18") (pinfunction "EXPSDA1_18") (pintype "bidirectional"))
    )
    (net (code "93") (name "unconnected-(U$2-EXPSDA2-Pad19)") (class "Default")
      (node (ref "U$2") (pin "19") (pinfunction "EXPSDA2_19") (pintype "bidirectional"))
    )
  )
)
